# Ethernet.net
KiCad netlist of a schematic drawn in Altium Designer
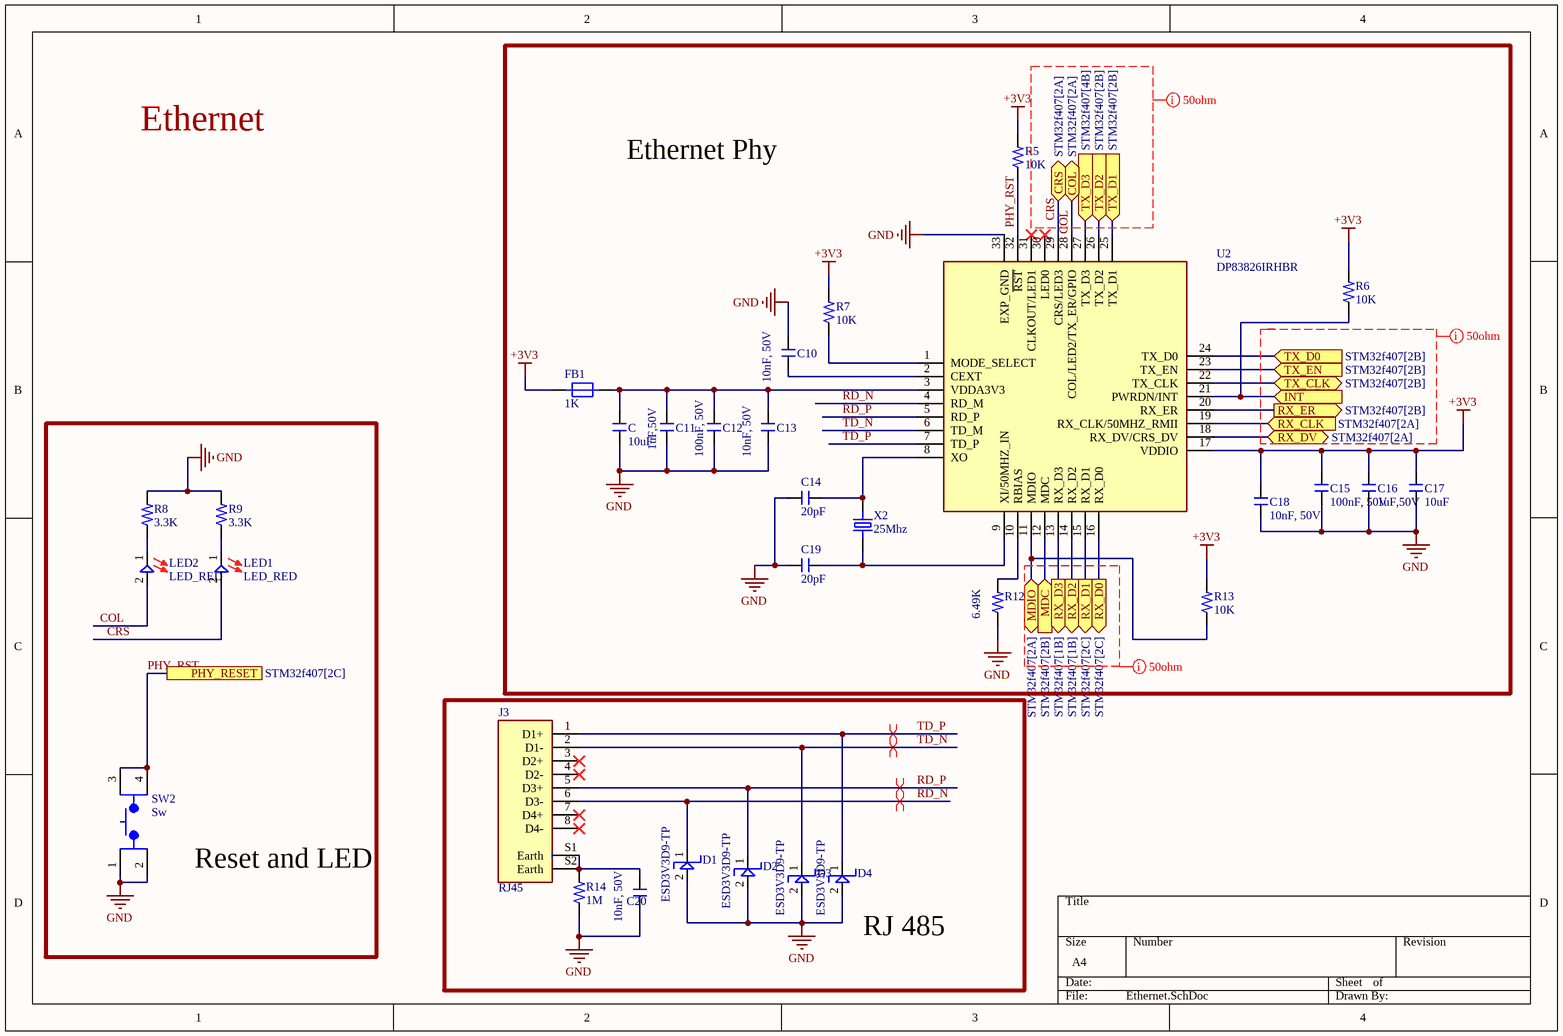
[diagram p0: Ethernet.SchDoc]

(export (version "E")
  (design (tool "Eeschema 10.0.6"))
  (components
    (comp (ref "C")
      (value "10uF")
      (footprint "Capacitor_1206_SMD")
      (description "Multilayer Ceramic Capacitor, 10 uF, 50 V, ï¿½ 10%, X7R, 1206 [3216 Metric]")
      (fields
        (field (name "MANUFACTURER") "Samsung")
        (field (name "MANUFACTURER PART NUMBER") "CL31B106KBHNNNE")
      )
      (libsource (lib "Schematics_Library_Hanif") (part "Cap_10uF_1206"))
    )
    (comp (ref "C10")
      (value "10nF, 50V")
      (footprint "Capacitor_0805")
      (description "Multilayer Ceramic Capacitors MLCC - SMD/SMT 50V 0.01uF X7R 0805 10% AEC-Q200")
      (fields
        (field (name "MANUFACTURER") "KEMET")
        (field (name "MANUFACTURER PART NUMBER") "C0805C103K5RECAUTO")
      )
      (libsource (lib "Schematics_Library_Hanif") (part "Cap_10nF_0805"))
    )
    (comp (ref "C11")
      (value "1uF,50V")
      (footprint "Capacitor_0805")
      (description "0805 1 uF 50 V ±5 % Tolerance X7R Surface Mount Multilayer Ceramic Capacitor")
      (fields
        (field (name "MANUFACTURER") "Yageo")
        (field (name "MANUFACTURER PART NUMBER") "CC0805JKX7R9BB105")
      )
      (libsource (lib "Schematics_Library_Hanif") (part "Cap_1uF_0805"))
    )
    (comp (ref "C12")
      (value "100nF, 50V")
      (footprint "Capacitor_0805")
      (description "Multilayer Ceramic Capacitor, 0.1 uF, 50 V, ï¿½ 10%, X7R, 0805 [2012 Metric]")
      (fields
        (field (name "MANUFACTURER") "Samsung")
        (field (name "MANUFACTURER PART NUMBER") "CL21B104KBCNNNC")
      )
      (libsource (lib "Schematics_Library_Hanif") (part "Cap_100nF_0805"))
    )
    (comp (ref "C13")
      (value "10nF, 50V")
      (footprint "Capacitor_0805")
      (description "Multilayer Ceramic Capacitors MLCC - SMD/SMT 50V 0.01uF X7R 0805 10% AEC-Q200")
      (fields
        (field (name "MANUFACTURER") "KEMET")
        (field (name "MANUFACTURER PART NUMBER") "C0805C103K5RECAUTO")
      )
      (libsource (lib "Schematics_Library_Hanif") (part "Cap_10nF_0805"))
    )
    (comp (ref "C14")
      (value "20pF")
      (footprint "Capacitor_0805")
      (description "Cap Ceramic 20pF 50V C0G 10% SMD 0805 125°C T/R")
      (fields
        (field (name "MANUFACTURER") "Kyocera AVX")
        (field (name "MANUFACTURER PART NUMBER") "08055A200KAT2A")
      )
      (libsource (lib "Schematics_Library_Hanif") (part "Cap_20pF_0805"))
    )
    (comp (ref "C15")
      (value "100nF, 50V")
      (footprint "Capacitor_0805")
      (description "Multilayer Ceramic Capacitor, 0.1 uF, 50 V, ï¿½ 10%, X7R, 0805 [2012 Metric]")
      (fields
        (field (name "MANUFACTURER") "Samsung")
        (field (name "MANUFACTURER PART NUMBER") "CL21B104KBCNNNC")
      )
      (libsource (lib "Schematics_Library_Hanif") (part "Cap_100nF_0805"))
    )
    (comp (ref "C16")
      (value "1uF,50V")
      (footprint "Capacitor_0805")
      (description "0805 1 uF 50 V ±5 % Tolerance X7R Surface Mount Multilayer Ceramic Capacitor")
      (fields
        (field (name "MANUFACTURER") "Yageo")
        (field (name "MANUFACTURER PART NUMBER") "CC0805JKX7R9BB105")
      )
      (libsource (lib "Schematics_Library_Hanif") (part "Cap_1uF_0805"))
    )
    (comp (ref "C17")
      (value "10uF")
      (footprint "Capacitor_1206_SMD")
      (description "Multilayer Ceramic Capacitor, 10 uF, 50 V, ï¿½ 10%, X7R, 1206 [3216 Metric]")
      (fields
        (field (name "MANUFACTURER") "Samsung")
        (field (name "MANUFACTURER PART NUMBER") "CL31B106KBHNNNE")
      )
      (libsource (lib "Schematics_Library_Hanif") (part "Cap_10uF_1206"))
    )
    (comp (ref "C18")
      (value "10nF, 50V")
      (footprint "Capacitor_0805")
      (description "Multilayer Ceramic Capacitors MLCC - SMD/SMT 50V 0.01uF X7R 0805 10% AEC-Q200")
      (fields
        (field (name "MANUFACTURER") "KEMET")
        (field (name "MANUFACTURER PART NUMBER") "C0805C103K5RECAUTO")
      )
      (libsource (lib "Schematics_Library_Hanif") (part "Cap_10nF_0805"))
    )
    (comp (ref "C19")
      (value "20pF")
      (footprint "Capacitor_0805")
      (description "Cap Ceramic 20pF 50V C0G 10% SMD 0805 125°C T/R")
      (fields
        (field (name "MANUFACTURER") "Kyocera AVX")
        (field (name "MANUFACTURER PART NUMBER") "08055A200KAT2A")
      )
      (libsource (lib "Schematics_Library_Hanif") (part "Cap_20pF_0805"))
    )
    (comp (ref "C20")
      (value "10nF, 50V")
      (footprint "Capacitor_0805")
      (description "Multilayer Ceramic Capacitors MLCC - SMD/SMT 50V 0.01uF X7R 0805 10% AEC-Q200")
      (fields
        (field (name "MANUFACTURER") "KEMET")
        (field (name "MANUFACTURER PART NUMBER") "C0805C103K5RECAUTO")
      )
      (libsource (lib "Schematics_Library_Hanif") (part "Cap_10nF_0805"))
    )
    (comp (ref "D1")
      (value "ESD3V3D9-TP")
      (footprint "SOD_923")
      (description "Trans Voltage Suppressor Diode, 100W, 3.3V V(RWM), Unidirectional, 1 Element, Silicon")
      (fields (field (name "MANUFACTURER") "MCC"))
      (libsource (lib "Schematics_Library_Hanif") (part "TVS DIODE 3.3V"))
    )
    (comp (ref "D2")
      (value "ESD3V3D9-TP")
      (footprint "SOD_923")
      (description "Trans Voltage Suppressor Diode, 100W, 3.3V V(RWM), Unidirectional, 1 Element, Silicon")
      (fields (field (name "MANUFACTURER") "MCC"))
      (libsource (lib "Schematics_Library_Hanif") (part "TVS DIODE 3.3V"))
    )
    (comp (ref "D3")
      (value "ESD3V3D9-TP")
      (footprint "SOD_923")
      (description "Trans Voltage Suppressor Diode, 100W, 3.3V V(RWM), Unidirectional, 1 Element, Silicon")
      (fields (field (name "MANUFACTURER") "MCC"))
      (libsource (lib "Schematics_Library_Hanif") (part "TVS DIODE 3.3V"))
    )
    (comp (ref "D4")
      (value "ESD3V3D9-TP")
      (footprint "SOD_923")
      (description "Trans Voltage Suppressor Diode, 100W, 3.3V V(RWM), Unidirectional, 1 Element, Silicon")
      (fields (field (name "MANUFACTURER") "MCC"))
      (libsource (lib "Schematics_Library_Hanif") (part "TVS DIODE 3.3V"))
    )
    (comp (ref "FB1")
      (value "1K")
      (footprint "FB_0805")
      (description "Ferrite Beads Multi-Layer High Current 1KOhm 25% 100MHz 1.6A 0.12Ohm DCR 0805 Automotive T/R")
      (fields
        (field (name "MANUFACTURER") "Murata")
        (field (name "MANUFACTURER PART NUMBER") "BLM21SP102SH1D")
      )
      (libsource (lib "Schematics_Library_Hanif") (part "FB_BLM21SP102SH1D"))
    )
    (comp (ref "J3")
      (value "RJ45")
      (footprint "RJ45_Right_Angle_90_degree")
      (description "Conn RJ-45 F 8 POS 2.54mm Solder RA Thru-Hole 8 Terminal 1 Port")
      (fields
        (field (name "MANUFACTURER") "Assmann")
        (field (name "MANUFACTURER PART NUMBER") "A-2004-2-4-LPS-N-R")
      )
      (libsource (lib "Schematics_Library_Hanif") (part "CON_LAN_RJ45"))
    )
    (comp (ref "LED1")
      (value "LED_RED")
      (footprint "LTST-C171KRKT")
      (fields
        (field (name "MANUFACTURER") "Vishay Lite-On")
        (field (name "MANUFACTURER PART NUMBER") "LTST-C171KRKT")
      )
      (libsource (lib "Schematics_Library_Hanif") (part "LED_RED_SMD"))
    )
    (comp (ref "LED2")
      (value "LED_RED")
      (footprint "LTST-C171KRKT")
      (fields
        (field (name "MANUFACTURER") "Vishay Lite-On")
        (field (name "MANUFACTURER PART NUMBER") "LTST-C171KRKT")
      )
      (libsource (lib "Schematics_Library_Hanif") (part "LED_RED_SMD"))
    )
    (comp (ref "R5")
      (value "10K")
      (footprint "Resistor_0603")
      (description "SMD Chip Resistor, 10 kOhm, ï¿½ 1%, 100 mW, 0603 [1608 Metric], Thick Film, General Purpose")
      (fields
        (field (name "MANUFACTURER") "Yageo")
        (field (name "MANUFACTURER PART NUMBER") "RC0603FR-0710KL")
      )
      (libsource (lib "Schematics_Library_Hanif") (part "R_10K_0603"))
    )
    (comp (ref "R6")
      (value "10K")
      (footprint "Resistor_0603")
      (description "SMD Chip Resistor, 10 kOhm, ï¿½ 1%, 100 mW, 0603 [1608 Metric], Thick Film, General Purpose")
      (fields
        (field (name "MANUFACTURER") "Yageo")
        (field (name "MANUFACTURER PART NUMBER") "RC0603FR-0710KL")
      )
      (libsource (lib "Schematics_Library_Hanif") (part "R_10K_0603"))
    )
    (comp (ref "R7")
      (value "10K")
      (footprint "Resistor_0603")
      (description "SMD Chip Resistor, 10 kOhm, ï¿½ 1%, 100 mW, 0603 [1608 Metric], Thick Film, General Purpose")
      (fields
        (field (name "MANUFACTURER") "Yageo")
        (field (name "MANUFACTURER PART NUMBER") "RC0603FR-0710KL")
      )
      (libsource (lib "Schematics_Library_Hanif") (part "R_10K_0603"))
    )
    (comp (ref "R8")
      (value "3.3K")
      (footprint "Resistor_0603")
      (description "Res Thick Film 0603 3.3K Ohm 1% 0.1W(1/10W) ±100ppm/C Pad SMD T/R")
      (fields
        (field (name "MANUFACTURER") "Walsin Technologies")
        (field (name "MANUFACTURER PART NUMBER") "WR06X3301FTL")
      )
      (libsource (lib "Schematics_Library_Hanif") (part "R_3.3K_0603"))
    )
    (comp (ref "R9")
      (value "3.3K")
      (footprint "Resistor_0603")
      (description "Res Thick Film 0603 3.3K Ohm 1% 0.1W(1/10W) ±100ppm/C Pad SMD T/R")
      (fields
        (field (name "MANUFACTURER") "Walsin Technologies")
        (field (name "MANUFACTURER PART NUMBER") "WR06X3301FTL")
      )
      (libsource (lib "Schematics_Library_Hanif") (part "R_3.3K_0603"))
    )
    (comp (ref "R12")
      (value "6.49K")
      (footprint "Resistor_0805")
      (description "SMD Chip Resistor, 6.49 kOhm, ï¿½ 1%, 125 mW, 0805 [2012 Metric], Thick Film, General Purpose")
      (fields
        (field (name "MANUFACTURER") "Yageo")
        (field (name "MANUFACTURER PART NUMBER") "RC0805FR-076K49L")
      )
      (libsource (lib "Schematics_Library_Hanif") (part "R_6.49K_0805"))
    )
    (comp (ref "R13")
      (value "10K")
      (footprint "Resistor_0603")
      (description "SMD Chip Resistor, 10 kOhm, ï¿½ 1%, 100 mW, 0603 [1608 Metric], Thick Film, General Purpose")
      (fields
        (field (name "MANUFACTURER") "Yageo")
        (field (name "MANUFACTURER PART NUMBER") "RC0603FR-0710KL")
      )
      (libsource (lib "Schematics_Library_Hanif") (part "R_10K_0603"))
    )
    (comp (ref "R14")
      (value "1M")
      (footprint "Resistor_1206_SMD")
      (description "Res Thick Film 1206 1M Ohm 1% 0.25W(1/4W) ±100ppm/C Molded SMD Paper T/R")
      (fields
        (field (name "MANUFACTURER") "Walsin Technologies")
        (field (name "MANUFACTURER PART NUMBER") "WR12X1004FTL")
      )
      (libsource (lib "Schematics_Library_Hanif") (part "R_1M_1206"))
    )
    (comp (ref "SW2")
      (value "Sw")
      (footprint "SW_Tactile_SMD")
      (description "TL3305A Series SPST 12 V 4.5 x 4.5 mm 260 gf Top Actuated SMT Tactile Switch")
      (fields
        (field (name "MANUFACTURER") "E-Switch")
        (field (name "MANUFACTURER PART NUMBER") "TL3305AF260QG")
      )
      (libsource (lib "Schematics_Library_Hanif") (part "SW_Tactile_SPST"))
    )
    (comp (ref "U2")
      (value "DP83826IRHBR")
      (footprint "32-VQFN (5x5)")
      (description "Ethernet PHY 10BASE-Te/00BASE-TX 10/100 Mbps 160mW 1.8V/3.3V 2-Pin VQFN Industrial")
      (fields (field (name "MANUFACTURER") "Texas Instruments"))
      (libsource (lib "Schematics_Library_Hanif") (part "IC_DP83826IRHBR"))
    )
    (comp (ref "X2")
      (value "25Mhz")
      (footprint "Xtal_314_240X47_SMD")
      (description "Crystal 25MHz ±30ppm (Tol) ±50ppm (Stability) 20pF 2-Pin HC-49/SDLF SMD T/R")
      (fields
        (field (name "MANUFACTURER") "Fox Electronics")
        (field (name "MANUFACTURER PART NUMBER") "FC4SDCBMF25.0-T1")
      )
      (libsource (lib "Schematics_Library_Hanif") (part "Xtal_25MHz"))
    )
  )
  (nets
    (net (code "1") (name "+3V3") (class "Default")
      (node (ref "C15") (pin "2") (pinfunction "2_2") (pintype "passive"))
      (node (ref "C16") (pin "2") (pinfunction "2_2") (pintype "passive"))
      (node (ref "C17") (pin "2") (pinfunction "2_2") (pintype "passive"))
      (node (ref "C18") (pin "2") (pinfunction "2_2") (pintype "passive"))
      (node (ref "FB1") (pin "1") (pinfunction "1_1") (pintype "passive"))
      (node (ref "R13") (pin "2") (pinfunction "2_2") (pintype "passive"))
      (node (ref "R5") (pin "2") (pinfunction "2_2") (pintype "passive"))
      (node (ref "R6") (pin "2") (pinfunction "2_2") (pintype "passive"))
      (node (ref "R7") (pin "2") (pinfunction "2_2") (pintype "passive"))
      (node (ref "U2") (pin "17") (pinfunction "VDDIO_17") (pintype "passive"))
    )
    (net (code "2") (name "/COL") (class "Default")
      (node (ref "LED2") (pin "2") (pinfunction "2_2") (pintype "passive"))
      (node (ref "U2") (pin "28") (pinfunction "COL/LED2/TX_ER/GPIO_28") (pintype "passive"))
    )
    (net (code "3") (name "/CRS") (class "Default")
      (node (ref "LED1") (pin "2") (pinfunction "2_2") (pintype "passive"))
      (node (ref "U2") (pin "29") (pinfunction "CRS/LED3_29") (pintype "passive"))
    )
    (net (code "4") (name "/INT") (class "Default")
      (node (ref "R6") (pin "1") (pinfunction "1_1") (pintype "passive"))
      (node (ref "U2") (pin "21") (pinfunction "PWRDN/INT_21") (pintype "passive"))
    )
    (net (code "5") (name "/MDC") (class "Default")
      (node (ref "U2") (pin "12") (pinfunction "MDC_12") (pintype "passive"))
    )
    (net (code "6") (name "/MDIO") (class "Default")
      (node (ref "R13") (pin "1") (pinfunction "1_1") (pintype "passive"))
      (node (ref "U2") (pin "11") (pinfunction "MDIO_11") (pintype "passive"))
    )
    (net (code "7") (name "/PHY_RST") (class "Default")
      (node (ref "R5") (pin "1") (pinfunction "1_1") (pintype "passive"))
      (node (ref "SW2") (pin "3") (pinfunction "3_3") (pintype "passive"))
      (node (ref "SW2") (pin "4") (pinfunction "4_4") (pintype "passive"))
      (node (ref "U2") (pin "32") (pinfunction "~{RST}_32") (pintype "passive"))
    )
    (net (code "8") (name "/RD_N") (class "Default")
      (node (ref "D1") (pin "1") (pinfunction "1_1") (pintype "passive"))
      (node (ref "J3") (pin "6") (pinfunction "D3-_6") (pintype "passive"))
      (node (ref "U2") (pin "4") (pinfunction "RD_M_4") (pintype "passive"))
    )
    (net (code "9") (name "/RD_P") (class "Default")
      (node (ref "D2") (pin "1") (pinfunction "1_1") (pintype "passive"))
      (node (ref "J3") (pin "5") (pinfunction "D3+_5") (pintype "passive"))
      (node (ref "U2") (pin "5") (pinfunction "RD_P_5") (pintype "passive"))
    )
    (net (code "10") (name "/RX_CLK") (class "Default")
      (node (ref "U2") (pin "19") (pinfunction "RX_CLK/50MHZ_RMII_19") (pintype "passive"))
    )
    (net (code "11") (name "/RX_D0") (class "Default")
      (node (ref "U2") (pin "16") (pinfunction "RX_D0_16") (pintype "passive"))
    )
    (net (code "12") (name "/RX_D1") (class "Default")
      (node (ref "U2") (pin "15") (pinfunction "RX_D1_15") (pintype "passive"))
    )
    (net (code "13") (name "/RX_D2") (class "Default")
      (node (ref "U2") (pin "14") (pinfunction "RX_D2_14") (pintype "passive"))
    )
    (net (code "14") (name "/RX_D3") (class "Default")
      (node (ref "U2") (pin "13") (pinfunction "RX_D3_13") (pintype "passive"))
    )
    (net (code "15") (name "/RX_DV") (class "Default")
      (node (ref "U2") (pin "18") (pinfunction "RX_DV/CRS_DV_18") (pintype "passive"))
    )
    (net (code "16") (name "/RX_ER") (class "Default")
      (node (ref "U2") (pin "20") (pinfunction "RX_ER_20") (pintype "passive"))
    )
    (net (code "17") (name "/TD_N") (class "Default")
      (node (ref "D3") (pin "1") (pinfunction "1_1") (pintype "passive"))
      (node (ref "J3") (pin "2") (pinfunction "D1-_2") (pintype "passive"))
      (node (ref "U2") (pin "6") (pinfunction "TD_M_6") (pintype "passive"))
    )
    (net (code "18") (name "/TD_P") (class "Default")
      (node (ref "D4") (pin "1") (pinfunction "1_1") (pintype "passive"))
      (node (ref "J3") (pin "1") (pinfunction "D1+_1") (pintype "passive"))
      (node (ref "U2") (pin "7") (pinfunction "TD_P_7") (pintype "passive"))
    )
    (net (code "19") (name "/TX_CLK") (class "Default")
      (node (ref "U2") (pin "22") (pinfunction "TX_CLK_22") (pintype "passive"))
    )
    (net (code "20") (name "/TX_D0") (class "Default")
      (node (ref "U2") (pin "24") (pinfunction "TX_D0_24") (pintype "passive"))
    )
    (net (code "21") (name "/TX_D1") (class "Default")
      (node (ref "U2") (pin "25") (pinfunction "TX_D1_25") (pintype "passive"))
    )
    (net (code "22") (name "/TX_D2") (class "Default")
      (node (ref "U2") (pin "26") (pinfunction "TX_D2_26") (pintype "passive"))
    )
    (net (code "23") (name "/TX_D3") (class "Default")
      (node (ref "U2") (pin "27") (pinfunction "TX_D3_27") (pintype "passive"))
    )
    (net (code "24") (name "/TX_EN") (class "Default")
      (node (ref "U2") (pin "23") (pinfunction "TX_EN_23") (pintype "passive"))
    )
    (net (code "25") (name "GND") (class "Default")
      (node (ref "C") (pin "1") (pinfunction "1_1") (pintype "passive"))
      (node (ref "C10") (pin "2") (pinfunction "2_2") (pintype "passive"))
      (node (ref "C11") (pin "1") (pinfunction "1_1") (pintype "passive"))
      (node (ref "C12") (pin "1") (pinfunction "1_1") (pintype "passive"))
      (node (ref "C13") (pin "1") (pinfunction "1_1") (pintype "passive"))
      (node (ref "C14") (pin "1") (pinfunction "1_1") (pintype "passive"))
      (node (ref "C15") (pin "1") (pinfunction "1_1") (pintype "passive"))
      (node (ref "C16") (pin "1") (pinfunction "1_1") (pintype "passive"))
      (node (ref "C17") (pin "1") (pinfunction "1_1") (pintype "passive"))
      (node (ref "C18") (pin "1") (pinfunction "1_1") (pintype "passive"))
      (node (ref "C19") (pin "1") (pinfunction "1_1") (pintype "passive"))
      (node (ref "C20") (pin "1") (pinfunction "1_1") (pintype "passive"))
      (node (ref "D1") (pin "2") (pinfunction "2_2") (pintype "passive"))
      (node (ref "D2") (pin "2") (pinfunction "2_2") (pintype "passive"))
      (node (ref "D3") (pin "2") (pinfunction "2_2") (pintype "passive"))
      (node (ref "D4") (pin "2") (pinfunction "2_2") (pintype "passive"))
      (node (ref "R12") (pin "1") (pinfunction "1_1") (pintype "passive"))
      (node (ref "R14") (pin "1") (pinfunction "1_1") (pintype "passive"))
      (node (ref "R8") (pin "2") (pinfunction "2_2") (pintype "passive"))
      (node (ref "R9") (pin "2") (pinfunction "2_2") (pintype "passive"))
      (node (ref "SW2") (pin "1") (pinfunction "1_1") (pintype "passive"))
      (node (ref "SW2") (pin "2") (pinfunction "2_2") (pintype "passive"))
      (node (ref "U2") (pin "33") (pinfunction "EXP_GND_33") (pintype "passive"))
    )
    (net (code "26") (name "Net-(C20-Pad2)") (class "Default")
      (node (ref "C20") (pin "2") (pinfunction "2_2") (pintype "passive"))
      (node (ref "J3") (pin "S1") (pinfunction "Earth_S1") (pintype "passive"))
      (node (ref "J3") (pin "S2") (pinfunction "Earth_S2") (pintype "passive"))
      (node (ref "R14") (pin "2") (pinfunction "2_2") (pintype "passive"))
    )
    (net (code "27") (name "Net-(LED1-Pad1)") (class "Default")
      (node (ref "LED1") (pin "1") (pinfunction "1_1") (pintype "passive"))
      (node (ref "R9") (pin "1") (pinfunction "1_1") (pintype "passive"))
    )
    (net (code "28") (name "Net-(LED2-Pad1)") (class "Default")
      (node (ref "LED2") (pin "1") (pinfunction "1_1") (pintype "passive"))
      (node (ref "R8") (pin "1") (pinfunction "1_1") (pintype "passive"))
    )
    (net (code "29") (name "Net-(U2-CEXT)") (class "Default")
      (node (ref "C10") (pin "1") (pinfunction "1_1") (pintype "passive"))
      (node (ref "U2") (pin "2") (pinfunction "CEXT_2") (pintype "passive"))
    )
    (net (code "30") (name "Net-(U2-MODE_SELECT)") (class "Default")
      (node (ref "R7") (pin "1") (pinfunction "1_1") (pintype "passive"))
      (node (ref "U2") (pin "1") (pinfunction "MODE_SELECT_1") (pintype "passive"))
    )
    (net (code "31") (name "Net-(U2-RBIAS)") (class "Default")
      (node (ref "R12") (pin "2") (pinfunction "2_2") (pintype "passive"))
      (node (ref "U2") (pin "10") (pinfunction "RBIAS_10") (pintype "passive"))
    )
    (net (code "32") (name "Net-(U2-VDDA3V3)") (class "Default")
      (node (ref "C") (pin "2") (pinfunction "2_2") (pintype "passive"))
      (node (ref "C11") (pin "2") (pinfunction "2_2") (pintype "passive"))
      (node (ref "C12") (pin "2") (pinfunction "2_2") (pintype "passive"))
      (node (ref "C13") (pin "2") (pinfunction "2_2") (pintype "passive"))
      (node (ref "FB1") (pin "2") (pinfunction "2_2") (pintype "passive"))
      (node (ref "U2") (pin "3") (pinfunction "VDDA3V3_3") (pintype "passive"))
    )
    (net (code "33") (name "Net-(U2-XI{slash}50MHZ_IN)") (class "Default")
      (node (ref "C19") (pin "2") (pinfunction "2_2") (pintype "passive"))
      (node (ref "U2") (pin "9") (pinfunction "XI/50MHZ_IN_9") (pintype "passive"))
      (node (ref "X2") (pin "1") (pinfunction "1_1") (pintype "passive"))
    )
    (net (code "34") (name "Net-(U2-XO)") (class "Default")
      (node (ref "C14") (pin "2") (pinfunction "2_2") (pintype "passive"))
      (node (ref "U2") (pin "8") (pinfunction "XO_8") (pintype "passive"))
      (node (ref "X2") (pin "2") (pinfunction "2_2") (pintype "passive"))
    )
    (net (code "35") (name "unconnected-(J3-D2+-Pad3)") (class "Default")
      (node (ref "J3") (pin "3") (pinfunction "D2+_3") (pintype "passive+no_connect"))
    )
    (net (code "36") (name "unconnected-(J3-D2--Pad4)") (class "Default")
      (node (ref "J3") (pin "4") (pinfunction "D2-_4") (pintype "passive+no_connect"))
    )
    (net (code "37") (name "unconnected-(J3-D4+-Pad7)") (class "Default")
      (node (ref "J3") (pin "7") (pinfunction "D4+_7") (pintype "passive+no_connect"))
    )
    (net (code "38") (name "unconnected-(J3-D4--Pad8)") (class "Default")
      (node (ref "J3") (pin "8") (pinfunction "D4-_8") (pintype "passive+no_connect"))
    )
    (net (code "39") (name "unconnected-(U2-CLKOUT{slash}LED1-Pad31)") (class "Default")
      (node (ref "U2") (pin "31") (pinfunction "CLKOUT/LED1_31") (pintype "passive+no_connect"))
    )
    (net (code "40") (name "unconnected-(U2-LED0-Pad30)") (class "Default")
      (node (ref "U2") (pin "30") (pinfunction "LED0_30") (pintype "passive+no_connect"))
    )
  )
)
